# S7_Audio_IMU_uSD.net
KiCad netlist of a schematic drawn in Altium Designer
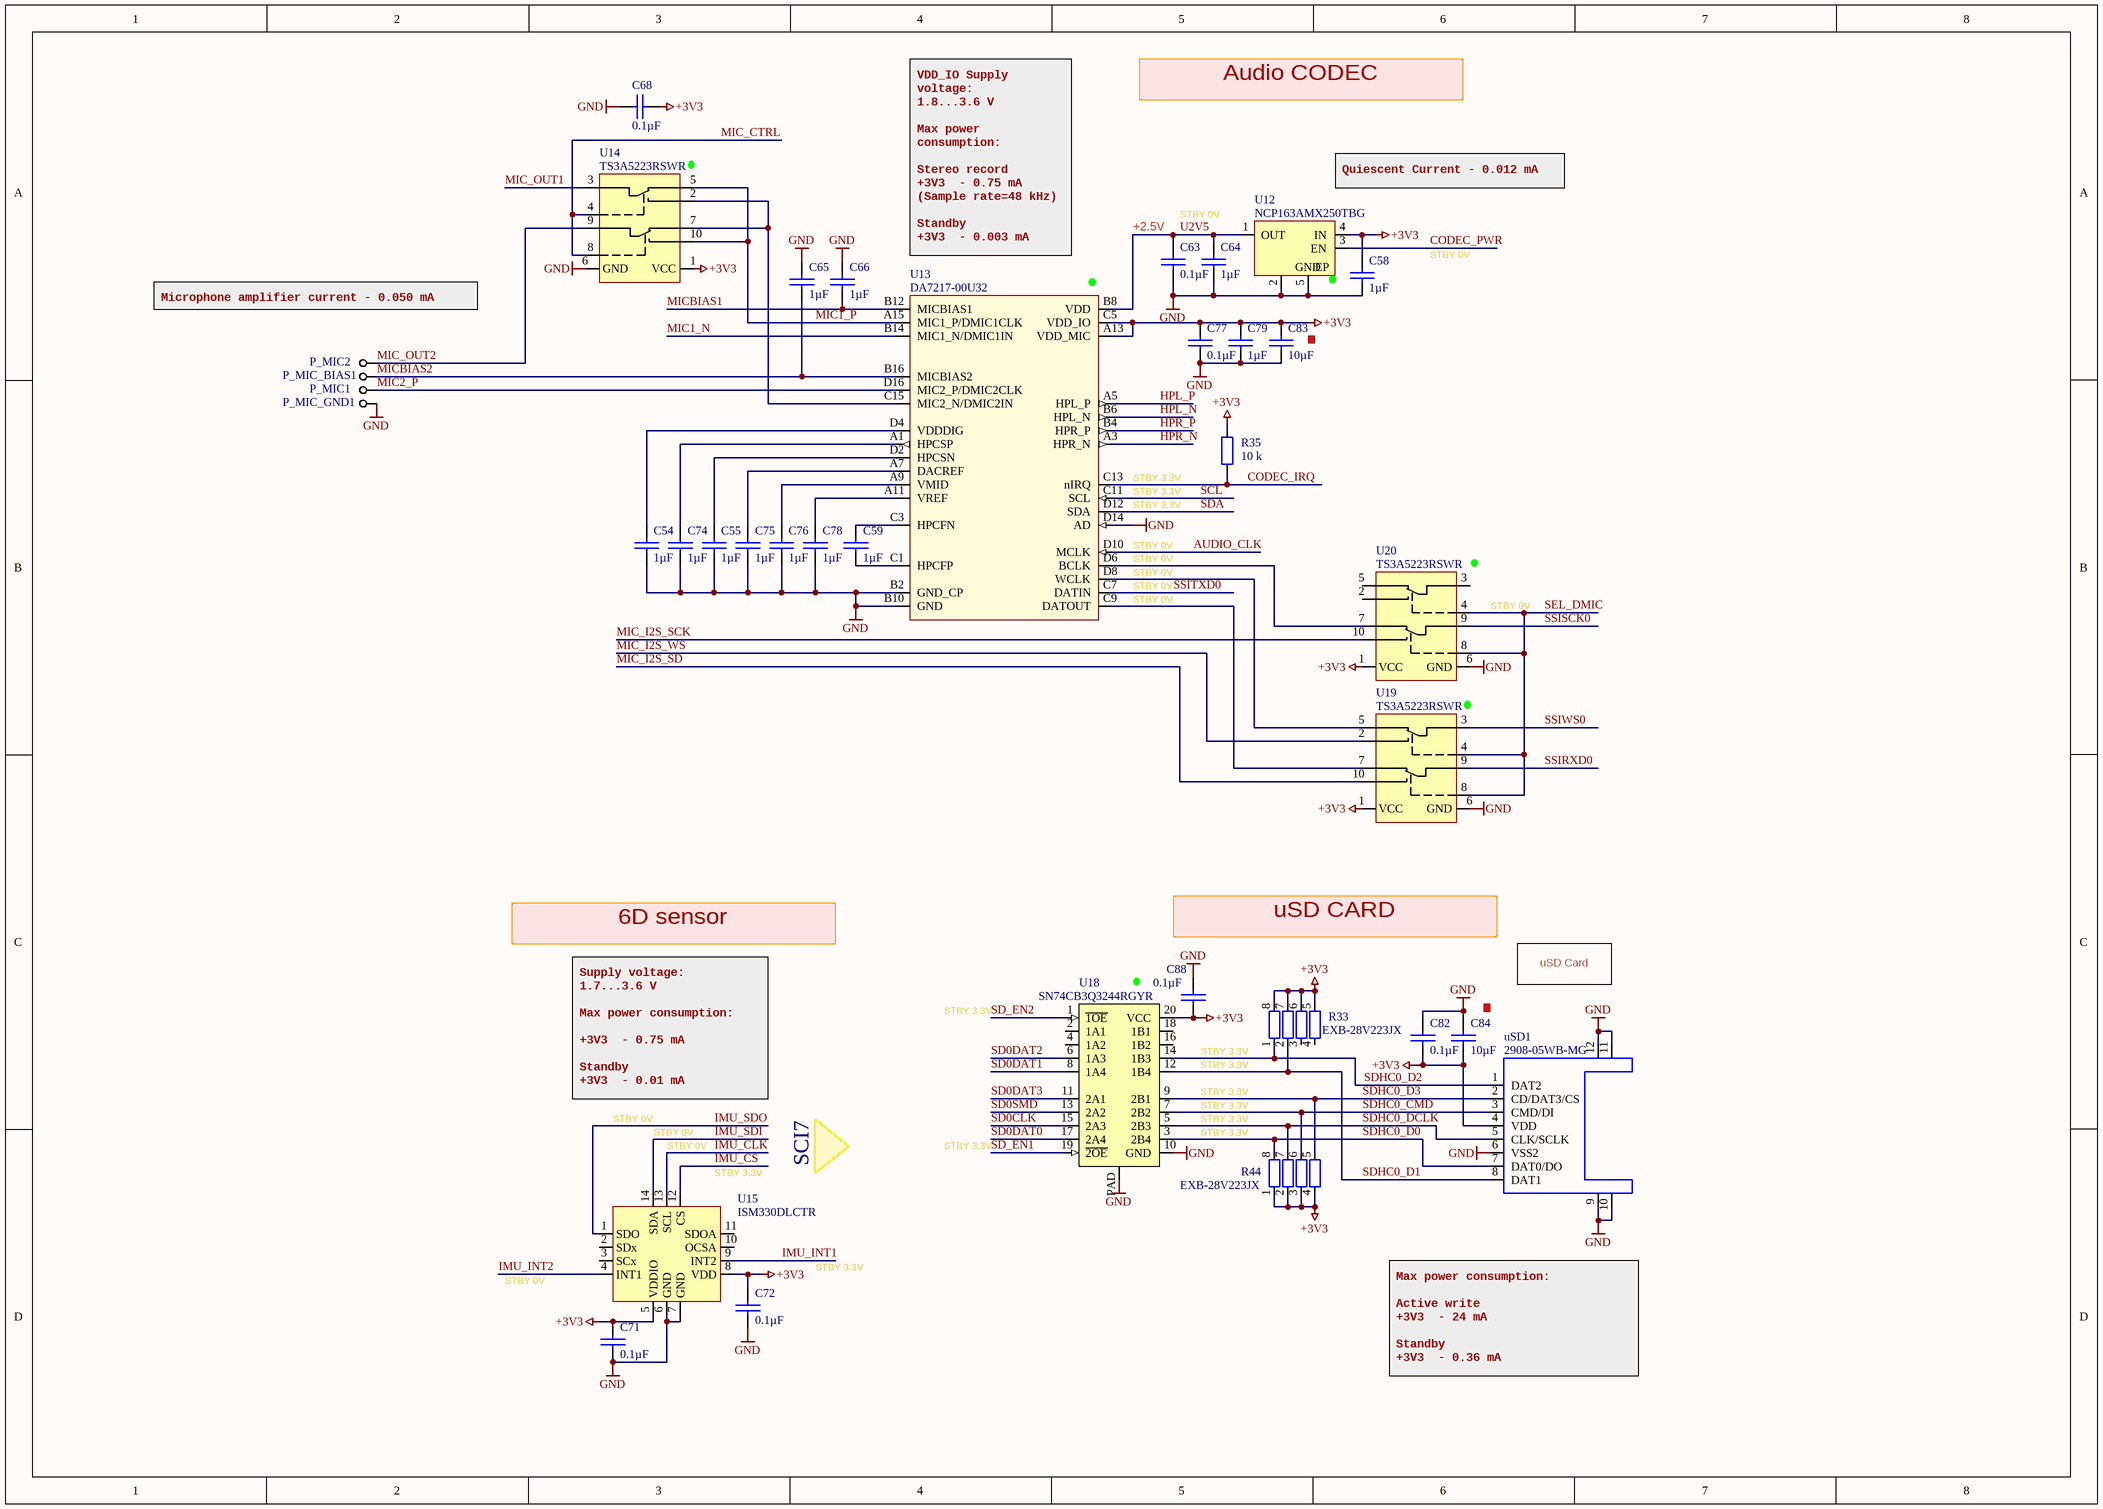
[diagram p0: S7_Audio_IMU_uSD.SchDoc]

(export (version "E")
  (design (tool "Eeschema 10.0.6"))
  (components
    (comp (ref "C54")
      (value "1µF")
      (footprint "0402 CAP")
      (description "1µF, ±20%, 25V, X5R, 0402 (1005 Metric), -55°C ~ 85°C, -, General Purpose")
      (fields (field (name "PART NUMBER") "TMK105BJ105MV-F") (field (name "MANUFACTURER") "Taiyo Yuden"))
      (libsource (lib "ea_PassivComps") (part "Capacitor"))
    )
    (comp (ref "C55")
      (value "1µF")
      (footprint "0402 CAP")
      (description "1µF, ±20%, 25V, X5R, 0402 (1005 Metric), -55°C ~ 85°C, -, General Purpose")
      (fields (field (name "PART NUMBER") "TMK105BJ105MV-F") (field (name "MANUFACTURER") "Taiyo Yuden"))
      (libsource (lib "ea_PassivComps") (part "Capacitor"))
    )
    (comp (ref "C58")
      (value "1µF")
      (footprint "0402 CAP")
      (description "1µF, ±20%, 25V, X5R, 0402 (1005 Metric), -55°C ~ 85°C, -, General Purpose")
      (fields (field (name "PART NUMBER") "TMK105BJ105MV-F") (field (name "MANUFACTURER") "Taiyo Yuden"))
      (libsource (lib "ea_PassivComps") (part "Capacitor"))
    )
    (comp (ref "C59")
      (value "1µF")
      (footprint "0402 CAP")
      (description "1µF, ±20%, 25V, X5R, 0402 (1005 Metric), -55°C ~ 85°C, -, General Purpose")
      (fields (field (name "PART NUMBER") "TMK105BJ105MV-F") (field (name "MANUFACTURER") "Taiyo Yuden"))
      (libsource (lib "ea_PassivComps") (part "Capacitor"))
    )
    (comp (ref "C63")
      (value "0.1µF")
      (footprint "0402 CAP")
      (description "0.1µF, ±10%, 50V, X7R, 0402 (1005 Metric), -55°C ~ 125°C, -, General Purpose")
      (fields
        (field (name "PART NUMBER") "0402B104K500CT")
        (field (name "MANUFACTURER") "Walsin Technology Corporation")
      )
      (libsource (lib "ea_PassivComps") (part "Capacitor"))
    )
    (comp (ref "C64")
      (value "1µF")
      (footprint "0402 CAP")
      (description "1µF, ±20%, 25V, X5R, 0402 (1005 Metric), -55°C ~ 85°C, -, General Purpose")
      (fields (field (name "PART NUMBER") "TMK105BJ105MV-F") (field (name "MANUFACTURER") "Taiyo Yuden"))
      (libsource (lib "ea_PassivComps") (part "Capacitor"))
    )
    (comp (ref "C65")
      (value "1µF")
      (footprint "0402 CAP")
      (description "1µF, ±20%, 25V, X5R, 0402 (1005 Metric), -55°C ~ 85°C, -, General Purpose")
      (fields (field (name "PART NUMBER") "TMK105BJ105MV-F") (field (name "MANUFACTURER") "Taiyo Yuden"))
      (libsource (lib "ea_PassivComps") (part "Capacitor"))
    )
    (comp (ref "C66")
      (value "1µF")
      (footprint "0402 CAP")
      (description "1µF, ±20%, 25V, X5R, 0402 (1005 Metric), -55°C ~ 85°C, -, General Purpose")
      (fields (field (name "PART NUMBER") "TMK105BJ105MV-F") (field (name "MANUFACTURER") "Taiyo Yuden"))
      (libsource (lib "ea_PassivComps") (part "Capacitor"))
    )
    (comp (ref "C68")
      (value "0.1µF")
      (footprint "0402 CAP")
      (description "0.1µF, ±10%, 50V, X7R, 0402 (1005 Metric), -55°C ~ 125°C, -, General Purpose")
      (fields
        (field (name "PART NUMBER") "0402B104K500CT")
        (field (name "MANUFACTURER") "Walsin Technology Corporation")
      )
      (libsource (lib "ea_PassivComps") (part "Capacitor"))
    )
    (comp (ref "C71")
      (value "0.1µF")
      (footprint "0402 CAP")
      (description "0.1µF, ±10%, 50V, X7R, 0402 (1005 Metric), -55°C ~ 125°C, -, General Purpose")
      (fields
        (field (name "PART NUMBER") "0402B104K500CT")
        (field (name "MANUFACTURER") "Walsin Technology Corporation")
      )
      (libsource (lib "ea_PassivComps") (part "Capacitor"))
    )
    (comp (ref "C72")
      (value "0.1µF")
      (footprint "0402 CAP")
      (description "0.1µF, ±10%, 50V, X7R, 0402 (1005 Metric), -55°C ~ 125°C, -, General Purpose")
      (fields
        (field (name "PART NUMBER") "0402B104K500CT")
        (field (name "MANUFACTURER") "Walsin Technology Corporation")
      )
      (libsource (lib "ea_PassivComps") (part "Capacitor"))
    )
    (comp (ref "C74")
      (value "1µF")
      (footprint "0402 CAP")
      (description "1µF, ±20%, 25V, X5R, 0402 (1005 Metric), -55°C ~ 85°C, -, General Purpose")
      (fields (field (name "PART NUMBER") "TMK105BJ105MV-F") (field (name "MANUFACTURER") "Taiyo Yuden"))
      (libsource (lib "ea_PassivComps") (part "Capacitor"))
    )
    (comp (ref "C75")
      (value "1µF")
      (footprint "0402 CAP")
      (description "1µF, ±20%, 25V, X5R, 0402 (1005 Metric), -55°C ~ 85°C, -, General Purpose")
      (fields (field (name "PART NUMBER") "TMK105BJ105MV-F") (field (name "MANUFACTURER") "Taiyo Yuden"))
      (libsource (lib "ea_PassivComps") (part "Capacitor"))
    )
    (comp (ref "C76")
      (value "1µF")
      (footprint "0402 CAP")
      (description "1µF, ±20%, 25V, X5R, 0402 (1005 Metric), -55°C ~ 85°C, -, General Purpose")
      (fields (field (name "PART NUMBER") "TMK105BJ105MV-F") (field (name "MANUFACTURER") "Taiyo Yuden"))
      (libsource (lib "ea_PassivComps") (part "Capacitor"))
    )
    (comp (ref "C77")
      (value "0.1µF")
      (footprint "0402 CAP")
      (description "0.1µF, ±10%, 50V, X7R, 0402 (1005 Metric), -55°C ~ 125°C, -, General Purpose")
      (fields
        (field (name "PART NUMBER") "0402B104K500CT")
        (field (name "MANUFACTURER") "Walsin Technology Corporation")
      )
      (libsource (lib "ea_PassivComps") (part "Capacitor"))
    )
    (comp (ref "C78")
      (value "1µF")
      (footprint "0402 CAP")
      (description "1µF, ±20%, 25V, X5R, 0402 (1005 Metric), -55°C ~ 85°C, -, General Purpose")
      (fields (field (name "PART NUMBER") "TMK105BJ105MV-F") (field (name "MANUFACTURER") "Taiyo Yuden"))
      (libsource (lib "ea_PassivComps") (part "Capacitor"))
    )
    (comp (ref "C79")
      (value "1µF")
      (footprint "0402 CAP")
      (description "1µF, ±20%, 25V, X5R, 0402 (1005 Metric), -55°C ~ 85°C, -, General Purpose")
      (fields (field (name "PART NUMBER") "TMK105BJ105MV-F") (field (name "MANUFACTURER") "Taiyo Yuden"))
      (libsource (lib "ea_PassivComps") (part "Capacitor"))
    )
    (comp (ref "C82")
      (value "0.1µF")
      (footprint "0402 CAP")
      (description "0.1µF, ±10%, 50V, X7R, 0402 (1005 Metric), -55°C ~ 125°C, -, General Purpose")
      (fields
        (field (name "PART NUMBER") "0402B104K500CT")
        (field (name "MANUFACTURER") "Walsin Technology Corporation")
      )
      (libsource (lib "ea_PassivComps") (part "Capacitor"))
    )
    (comp (ref "C83")
      (value "10µF")
      (footprint "0603 CAP")
      (description "10µF, ±10%, 16V, X5R, 0603 (1608 Metric), -55°C ~ 85°C, -, Automotive")
      (fields
        (field (name "PART NUMBER") "GRT188R61C106KE13D")
        (field (name "MANUFACTURER") "Murata Electronics North America")
      )
      (libsource (lib "ea_PassivComps") (part "Capacitor"))
    )
    (comp (ref "C84")
      (value "10µF")
      (footprint "0603 CAP")
      (description "10µF, ±10%, 16V, X5R, 0603 (1608 Metric), -55°C ~ 85°C, -, Automotive")
      (fields
        (field (name "PART NUMBER") "GRT188R61C106KE13D")
        (field (name "MANUFACTURER") "Murata Electronics North America")
      )
      (libsource (lib "ea_PassivComps") (part "Capacitor"))
    )
    (comp (ref "C88")
      (value "0.1µF")
      (footprint "0402 CAP")
      (description "0.1µF, ±10%, 50V, X7R, 0402 (1005 Metric), -55°C ~ 125°C, -, General Purpose")
      (fields
        (field (name "PART NUMBER") "0402B104K500CT")
        (field (name "MANUFACTURER") "Walsin Technology Corporation")
      )
      (libsource (lib "ea_PassivComps") (part "Capacitor"))
    )
    (comp (ref "P_MIC1")
      (value "PIN_TOP_1.5x2")
      (footprint "PIN_TOP_1.5x2")
      (description "Pin on TOP layer 1.5 x 2 mm")
      (libsource (lib "ea_Contacts") (part "PIN_TOP_1.5x2"))
    )
    (comp (ref "P_MIC2")
      (value "PIN_TOP_1.5x2")
      (footprint "PIN_TOP_1.5x2")
      (description "Pin on TOP layer 1.5 x 2 mm")
      (libsource (lib "ea_Contacts") (part "PIN_TOP_1.5x2"))
    )
    (comp (ref "P_MIC_BIAS1")
      (value "PIN_TOP_1.5x2")
      (footprint "PIN_TOP_1.5x2")
      (description "Pin on TOP layer 1.5 x 2 mm")
      (libsource (lib "ea_Contacts") (part "PIN_TOP_1.5x2"))
    )
    (comp (ref "P_MIC_GND1")
      (value "PIN_TOP_1.5x2")
      (footprint "PIN_TOP_1.5x2")
      (description "Pin on TOP layer 1.5 x 2 mm")
      (libsource (lib "ea_Contacts") (part "PIN_TOP_1.5x2"))
    )
    (comp (ref "R33")
      (value "EXB-28V223JX")
      (footprint "EXB28V 2x1 mm")
      (description "22k Ohm ±5%,  4 Resistor, -55°C ~ 125°C,(2.00mm x 1.00mm)")
      (fields (field (name "MANUFACTURER") "Panasonic Electronic Components") (field (name "TOLERANCE") "5%"))
      (libsource (lib "ea_Resistors") (part "EXB-28V223JX"))
    )
    (comp (ref "R35")
      (value "10 k")
      (footprint "0402")
      (fields
        (field (name "MANUFACTURER") "Stackpole Electronics Inc")
        (field (name "TOLERANCE") "±1%")
        (field (name "VOLTAGE") "75V")
      )
      (libsource (lib "ea_PassivComps") (part "Resistor"))
    )
    (comp (ref "R44")
      (value "EXB-28V223JX")
      (footprint "EXB28V 2x1 mm")
      (description "22k Ohm ±5%,  4 Resistor, -55°C ~ 125°C,(2.00mm x 1.00mm)")
      (fields (field (name "MANUFACTURER") "Panasonic Electronic Components") (field (name "TOLERANCE") "5%"))
      (libsource (lib "ea_Resistors") (part "EXB-28V223JX"))
    )
    (comp (ref "U12")
      (value "NCP163AMX250TBG")
      (footprint "4-XDFN")
      (description "LDO 2.5V, 250 mA, Vin < 5.5V, Iq < 20uA, -40..+125 C,  4-XDFN (1x1)")
      (fields
        (field (name "MANUFACTURER") "ON Semiconductor")
        (field (name "PARTNUM") "NCP163AMX250TBGOSCT-ND")
      )
      (libsource (lib "ea_IC_Power_Reg_Ref_Sw") (part "NCP163AMX250TBG"))
    )
    (comp (ref "U13")
      (value "DA7217-00U32")
      (footprint "Dilaog 34-WLCSP (4.57x1.98)")
      (description "Low power CODEC, 24 b, 2/2, I²C, I²S,  1.5V ~ 3.6V,  -25°C ~ 85°C, 34-WLCSP (4.57x1.98)")
      (fields
        (field (name "MANUFACTURER") "Dialog Semiconductor GmbH")
        (field (name "PARTNUM") "1564-1043-1-ND")
      )
      (libsource (lib "ea_IC_audio") (part "DA7217-00U32"))
    )
    (comp (ref "U14")
      (value "TS3A5223RSWR")
      (footprint "uQFN-10")
      (description "2 Circuit IC Switch 2:1 600 mOhm,-40°C ~ 85°C, 10-UQFN (1.8x1.4)")
      (fields (field (name "MANUFACTURER") "Texas Instruments") (field (name "PARTNUM") "296-35687-1-ND"))
      (libsource (lib "ea_IC_AnalogMux") (part "TS3A5223RSWR"))
    )
    (comp (ref "U15")
      (value "ISM330DLCTR")
      (footprint "LGA-14 BOSCH")
      (description "Accelerometer, Gyroscope, Temperature, 3 Axis Sensor I²C, SPI , -40°C ~ 85°C, 14-LGA (2.5x3)")
      (fields (field (name "MANUFACTURER") "STMicroelectronics") (field (name "PARTNUM") "497-17583-1-ND"))
      (libsource (lib "ea_IC_sensors") (part "ISM330DLCTR"))
    )
    (comp (ref "U18")
      (value "SN74CB3Q3244RGYR")
      (footprint "TI_PVQFN-N20")
      (description "Bus Switch 4 x 1:1, 2.3V ~ 3.6V,  -40°C ~ 85°C, 20-VQFN (3.5x4.5)")
      (fields (field (name "MANUFACTURER") "Texas Instruments") (field (name "PARTNUM") "296-19127-1-ND"))
      (libsource (lib "ea_IC_registers_buffers") (part "SN74CB3Q3244RGYR"))
    )
    (comp (ref "U19")
      (value "TS3A5223RSWR")
      (footprint "uQFN-10")
      (description "2 Circuit IC Switch 2:1 600 mOhm,-40°C ~ 85°C, 10-UQFN (1.8x1.4)")
      (fields (field (name "MANUFACTURER") "Texas Instruments") (field (name "PARTNUM") "296-35687-1-ND"))
      (libsource (lib "") (part "TS3A5223RSWR_1"))
    )
    (comp (ref "U20")
      (value "TS3A5223RSWR")
      (footprint "uQFN-10")
      (description "2 Circuit IC Switch 2:1 600 mOhm,-40°C ~ 85°C, 10-UQFN (1.8x1.4)")
      (fields (field (name "MANUFACTURER") "Texas Instruments") (field (name "PARTNUM") "296-35687-1-ND"))
      (libsource (lib "") (part "TS3A5223RSWR_1"))
    )
    (comp (ref "uSD1")
      (value "2908-05WB-MG")
      (footprint "2908-05WB-MG")
      (description "microSD cadr holder")
      (fields
        (field (name "MANUFACTURER") "Amphenol Commercial Products")
        (field (name "PARTNUM") "101-00660-68-6-1-ND")
      )
      (libsource (lib "ea_CARD_holders") (part "2908-05WB-MG"))
    )
  )
  (nets
    (net (code "1") (name "+3V3") (class "Default")
      (node (ref "C58") (pin "1") (pinfunction "1_1") (pintype "passive"))
      (node (ref "C68") (pin "2") (pinfunction "2_2") (pintype "passive"))
      (node (ref "C71") (pin "1") (pinfunction "1_1") (pintype "passive"))
      (node (ref "C72") (pin "1") (pinfunction "1_1") (pintype "passive"))
      (node (ref "C77") (pin "1") (pinfunction "1_1") (pintype "passive"))
      (node (ref "C79") (pin "1") (pinfunction "1_1") (pintype "passive"))
      (node (ref "C82") (pin "2") (pinfunction "2_2") (pintype "passive"))
      (node (ref "C83") (pin "1") (pinfunction "1_1") (pintype "passive"))
      (node (ref "C84") (pin "2") (pinfunction "2_2") (pintype "passive"))
      (node (ref "C88") (pin "2") (pinfunction "2_2") (pintype "passive"))
      (node (ref "R33") (pin "5") (pinfunction "5_5") (pintype "passive"))
      (node (ref "R33") (pin "6") (pinfunction "6_6") (pintype "passive"))
      (node (ref "R33") (pin "7") (pinfunction "7_7") (pintype "passive"))
      (node (ref "R33") (pin "8") (pinfunction "8_8") (pintype "passive"))
      (node (ref "R35") (pin "2") (pinfunction "2_2") (pintype "passive"))
      (node (ref "R44") (pin "1") (pinfunction "1_1") (pintype "passive"))
      (node (ref "R44") (pin "2") (pinfunction "2_2") (pintype "passive"))
      (node (ref "R44") (pin "3") (pinfunction "3_3") (pintype "passive"))
      (node (ref "R44") (pin "4") (pinfunction "4_4") (pintype "passive"))
      (node (ref "U12") (pin "4") (pinfunction "IN_4") (pintype "power_in"))
      (node (ref "U13") (pin "A13") (pinfunction "VDD_MIC_A13") (pintype "power_in"))
      (node (ref "U13") (pin "C5") (pinfunction "VDD_IO_C5") (pintype "power_in"))
      (node (ref "U14") (pin "1") (pinfunction "VCC_1") (pintype "passive"))
      (node (ref "U15") (pin "5") (pinfunction "VDDIO_5") (pintype "passive"))
      (node (ref "U15") (pin "8") (pinfunction "VDD_8") (pintype "passive"))
      (node (ref "U18") (pin "20") (pinfunction "VCC_20") (pintype "power_in"))
      (node (ref "U19") (pin "1") (pinfunction "VCC_1") (pintype "passive"))
      (node (ref "U20") (pin "1") (pinfunction "VCC_1") (pintype "passive"))
      (node (ref "uSD1") (pin "4") (pinfunction "VDD_4") (pintype "passive"))
    )
    (net (code "2") (name "/AUDIO_CLK") (class "Default")
      (node (ref "U13") (pin "D10") (pinfunction "MCLK_D10") (pintype "input"))
    )
    (net (code "3") (name "/CODEC_IRQ") (class "Default")
      (node (ref "R35") (pin "1") (pinfunction "1_1") (pintype "passive"))
      (node (ref "U13") (pin "C13") (pinfunction "nIRQ_C13") (pintype "bidirectional"))
    )
    (net (code "4") (name "/CODEC_PWR") (class "Default")
      (node (ref "U12") (pin "3") (pinfunction "EN_3") (pintype "power_in"))
    )
    (net (code "5") (name "/HPL_N") (class "Default")
      (node (ref "U13") (pin "B6") (pinfunction "HPL_N_B6") (pintype "output"))
    )
    (net (code "6") (name "/HPL_P") (class "Default")
      (node (ref "U13") (pin "A5") (pinfunction "HPL_P_A5") (pintype "output"))
    )
    (net (code "7") (name "/HPR_N") (class "Default")
      (node (ref "U13") (pin "A3") (pinfunction "HPR_N_A3") (pintype "output"))
    )
    (net (code "8") (name "/HPR_P") (class "Default")
      (node (ref "U13") (pin "B4") (pinfunction "HPR_P_B4") (pintype "output"))
    )
    (net (code "9") (name "/IMU_CLK") (class "Default")
      (node (ref "U15") (pin "13") (pinfunction "SCL_13") (pintype "passive"))
    )
    (net (code "10") (name "/IMU_CS") (class "Default")
      (node (ref "U15") (pin "12") (pinfunction "CS_12") (pintype "passive"))
    )
    (net (code "11") (name "/IMU_INT1") (class "Default")
      (node (ref "U15") (pin "9") (pinfunction "INT2_9") (pintype "passive"))
    )
    (net (code "12") (name "/IMU_INT2") (class "Default")
      (node (ref "U15") (pin "4") (pinfunction "INT1_4") (pintype "passive"))
    )
    (net (code "13") (name "/IMU_SDI") (class "Default")
      (node (ref "U15") (pin "14") (pinfunction "SDA_14") (pintype "passive"))
    )
    (net (code "14") (name "/IMU_SDO") (class "Default")
      (node (ref "U15") (pin "1") (pinfunction "SDO_1") (pintype "passive"))
    )
    (net (code "15") (name "/MIC1_N") (class "Default")
      (node (ref "U13") (pin "B14") (pinfunction "MIC1_N/DMIC1IN_B14") (pintype "bidirectional"))
    )
    (net (code "16") (name "/MIC1_P") (class "Default")
      (node (ref "U13") (pin "A15") (pinfunction "MIC1_P/DMIC1CLK_A15") (pintype "bidirectional"))
      (node (ref "U14") (pin "10") (pinfunction "NO2_10") (pintype "passive"))
      (node (ref "U14") (pin "5") (pinfunction "NC1_5") (pintype "passive"))
    )
    (net (code "17") (name "/MIC2_P") (class "Default")
      (node (ref "P_MIC1") (pin "1") (pinfunction "1_1") (pintype "passive"))
      (node (ref "U13") (pin "D16") (pinfunction "MIC2_P/DMIC2CLK_D16") (pintype "bidirectional"))
    )
    (net (code "18") (name "/MICBIAS1") (class "Default")
      (node (ref "C66") (pin "2") (pinfunction "2_2") (pintype "passive"))
      (node (ref "U13") (pin "B12") (pinfunction "MICBIAS1_B12") (pintype "bidirectional"))
    )
    (net (code "19") (name "/MICBIAS2") (class "Default")
      (node (ref "C65") (pin "2") (pinfunction "2_2") (pintype "passive"))
      (node (ref "P_MIC_BIAS1") (pin "1") (pinfunction "1_1") (pintype "passive"))
      (node (ref "U13") (pin "B16") (pinfunction "MICBIAS2_B16") (pintype "bidirectional"))
    )
    (net (code "20") (name "/MIC_CTRL") (class "Default")
      (node (ref "U14") (pin "4") (pinfunction "SEL1_4") (pintype "passive"))
      (node (ref "U14") (pin "8") (pinfunction "SEL2_8") (pintype "passive"))
    )
    (net (code "21") (name "/MIC_I2S_SCK") (class "Default")
      (node (ref "U20") (pin "10") (pinfunction "NO2_10") (pintype "passive"))
    )
    (net (code "22") (name "/MIC_I2S_SD") (class "Default")
      (node (ref "U19") (pin "10") (pinfunction "NO2_10") (pintype "passive"))
    )
    (net (code "23") (name "/MIC_I2S_WS") (class "Default")
      (node (ref "U19") (pin "2") (pinfunction "NO1_2") (pintype "passive"))
    )
    (net (code "24") (name "/MIC_OUT1") (class "Default")
      (node (ref "U14") (pin "3") (pinfunction "COM1_3") (pintype "passive"))
    )
    (net (code "25") (name "/MIC_OUT2") (class "Default")
      (node (ref "P_MIC2") (pin "1") (pinfunction "1_1") (pintype "passive"))
      (node (ref "U14") (pin "9") (pinfunction "COM2_9") (pintype "passive"))
    )
    (net (code "26") (name "/SCL") (class "Default")
      (node (ref "U13") (pin "C11") (pinfunction "SCL_C11") (pintype "input"))
    )
    (net (code "27") (name "/SD0CLK") (class "Default")
      (node (ref "U18") (pin "15") (pinfunction "2A3_15") (pintype "bidirectional"))
    )
    (net (code "28") (name "/SD0DAT0") (class "Default")
      (node (ref "U18") (pin "17") (pinfunction "2A4_17") (pintype "bidirectional"))
    )
    (net (code "29") (name "/SD0DAT1") (class "Default")
      (node (ref "U18") (pin "8") (pinfunction "1A4_8") (pintype "bidirectional"))
    )
    (net (code "30") (name "/SD0DAT2") (class "Default")
      (node (ref "U18") (pin "6") (pinfunction "1A3_6") (pintype "bidirectional"))
    )
    (net (code "31") (name "/SD0DAT3") (class "Default")
      (node (ref "U18") (pin "11") (pinfunction "2A1_11") (pintype "bidirectional"))
    )
    (net (code "32") (name "/SD0SMD") (class "Default")
      (node (ref "U18") (pin "13") (pinfunction "2A2_13") (pintype "bidirectional"))
    )
    (net (code "33") (name "/SDA") (class "Default")
      (node (ref "U13") (pin "D12") (pinfunction "SDA_D12") (pintype "bidirectional"))
    )
    (net (code "34") (name "/SDHC0_CMD") (class "Default")
      (node (ref "R44") (pin "6") (pinfunction "6_6") (pintype "passive"))
      (node (ref "U18") (pin "7") (pinfunction "2B2_7") (pintype "bidirectional"))
      (node (ref "uSD1") (pin "3") (pinfunction "CMD/DI_3") (pintype "passive"))
    )
    (net (code "35") (name "/SDHC0_D0") (class "Default")
      (node (ref "R44") (pin "8") (pinfunction "8_8") (pintype "passive"))
      (node (ref "U18") (pin "3") (pinfunction "2B4_3") (pintype "bidirectional"))
      (node (ref "uSD1") (pin "7") (pinfunction "DAT0/DO_7") (pintype "passive"))
    )
    (net (code "36") (name "/SDHC0_D1") (class "Default")
      (node (ref "R33") (pin "2") (pinfunction "2_2") (pintype "passive"))
      (node (ref "U18") (pin "12") (pinfunction "1B4_12") (pintype "bidirectional"))
      (node (ref "uSD1") (pin "8") (pinfunction "DAT1_8") (pintype "passive"))
    )
    (net (code "37") (name "/SDHC0_D2") (class "Default")
      (node (ref "R33") (pin "1") (pinfunction "1_1") (pintype "passive"))
      (node (ref "U18") (pin "14") (pinfunction "1B3_14") (pintype "bidirectional"))
      (node (ref "uSD1") (pin "1") (pinfunction "DAT2_1") (pintype "passive"))
    )
    (net (code "38") (name "/SDHC0_D3") (class "Default")
      (node (ref "R44") (pin "5") (pinfunction "5_5") (pintype "passive"))
      (node (ref "U18") (pin "9") (pinfunction "2B1_9") (pintype "bidirectional"))
      (node (ref "uSD1") (pin "2") (pinfunction "CD/DAT3/CS_2") (pintype "passive"))
    )
    (net (code "39") (name "/SDHC0_DCLK") (class "Default")
      (node (ref "R44") (pin "7") (pinfunction "7_7") (pintype "passive"))
      (node (ref "U18") (pin "5") (pinfunction "2B3_5") (pintype "bidirectional"))
      (node (ref "uSD1") (pin "5") (pinfunction "CLK/SCLK_5") (pintype "passive"))
    )
    (net (code "40") (name "/SD_EN1") (class "Default")
      (node (ref "U18") (pin "19") (pinfunction "~{2OE}_19") (pintype "input"))
    )
    (net (code "41") (name "/SD_EN2") (class "Default")
      (node (ref "U18") (pin "1") (pinfunction "~{1OE}_1") (pintype "input"))
    )
    (net (code "42") (name "/SEL_DMIC") (class "Default")
      (node (ref "U19") (pin "4") (pinfunction "SEL1_4") (pintype "passive"))
      (node (ref "U19") (pin "8") (pinfunction "SEL2_8") (pintype "passive"))
      (node (ref "U20") (pin "4") (pinfunction "SEL1_4") (pintype "passive"))
      (node (ref "U20") (pin "8") (pinfunction "SEL2_8") (pintype "passive"))
    )
    (net (code "43") (name "/SSIRXD0") (class "Default")
      (node (ref "U19") (pin "9") (pinfunction "COM2_9") (pintype "passive"))
    )
    (net (code "44") (name "/SSISCK0") (class "Default")
      (node (ref "U20") (pin "9") (pinfunction "COM2_9") (pintype "passive"))
    )
    (net (code "45") (name "/SSITXD0") (class "Default")
      (node (ref "U13") (pin "C7") (pinfunction "DATIN_C7") (pintype "bidirectional"))
    )
    (net (code "46") (name "/SSIWS0") (class "Default")
      (node (ref "U19") (pin "3") (pinfunction "COM1_3") (pintype "passive"))
    )
    (net (code "47") (name "/U2V5") (class "Default")
      (node (ref "C63") (pin "1") (pinfunction "1_1") (pintype "passive"))
      (node (ref "C64") (pin "1") (pinfunction "1_1") (pintype "passive"))
      (node (ref "U12") (pin "1") (pinfunction "OUT_1") (pintype "power_in"))
      (node (ref "U13") (pin "B8") (pinfunction "VDD_B8") (pintype "power_in"))
    )
    (net (code "48") (name "GND") (class "Default")
      (node (ref "C54") (pin "2") (pinfunction "2_2") (pintype "passive"))
      (node (ref "C55") (pin "2") (pinfunction "2_2") (pintype "passive"))
      (node (ref "C58") (pin "2") (pinfunction "2_2") (pintype "passive"))
      (node (ref "C63") (pin "2") (pinfunction "2_2") (pintype "passive"))
      (node (ref "C64") (pin "2") (pinfunction "2_2") (pintype "passive"))
      (node (ref "C65") (pin "1") (pinfunction "1_1") (pintype "passive"))
      (node (ref "C66") (pin "1") (pinfunction "1_1") (pintype "passive"))
      (node (ref "C68") (pin "1") (pinfunction "1_1") (pintype "passive"))
      (node (ref "C71") (pin "2") (pinfunction "2_2") (pintype "passive"))
      (node (ref "C72") (pin "2") (pinfunction "2_2") (pintype "passive"))
      (node (ref "C74") (pin "2") (pinfunction "2_2") (pintype "passive"))
      (node (ref "C75") (pin "2") (pinfunction "2_2") (pintype "passive"))
      (node (ref "C76") (pin "2") (pinfunction "2_2") (pintype "passive"))
      (node (ref "C77") (pin "2") (pinfunction "2_2") (pintype "passive"))
      (node (ref "C78") (pin "2") (pinfunction "2_2") (pintype "passive"))
      (node (ref "C79") (pin "2") (pinfunction "2_2") (pintype "passive"))
      (node (ref "C82") (pin "1") (pinfunction "1_1") (pintype "passive"))
      (node (ref "C83") (pin "2") (pinfunction "2_2") (pintype "passive"))
      (node (ref "C84") (pin "1") (pinfunction "1_1") (pintype "passive"))
      (node (ref "C88") (pin "1") (pinfunction "1_1") (pintype "passive"))
      (node (ref "P_MIC_GND1") (pin "1") (pinfunction "1_1") (pintype "passive"))
      (node (ref "U12") (pin "2") (pinfunction "GND_2") (pintype "power_in"))
      (node (ref "U12") (pin "5") (pinfunction "EP_5") (pintype "power_in"))
      (node (ref "U13") (pin "B10") (pinfunction "GND_B10") (pintype "power_in"))
      (node (ref "U13") (pin "B2") (pinfunction "GND_CP_B2") (pintype "power_in"))
      (node (ref "U13") (pin "D14") (pinfunction "AD_D14") (pintype "input"))
      (node (ref "U14") (pin "6") (pinfunction "GND_6") (pintype "passive"))
      (node (ref "U15") (pin "6") (pinfunction "GND_6") (pintype "passive"))
      (node (ref "U15") (pin "7") (pinfunction "GND_7") (pintype "passive"))
      (node (ref "U18") (pin "10") (pinfunction "GND_10") (pintype "power_in"))
      (node (ref "U18") (pin "PAD") (pinfunction "PAD_PAD") (pintype "passive"))
      (node (ref "U19") (pin "6") (pinfunction "GND_6") (pintype "passive"))
      (node (ref "U20") (pin "6") (pinfunction "GND_6") (pintype "passive"))
      (node (ref "uSD1") (pin "10") (pinfunction "WP_10") (pintype "passive"))
      (node (ref "uSD1") (pin "11") (pinfunction "GND_11") (pintype "passive"))
      (node (ref "uSD1") (pin "12") (pinfunction "GND_12") (pintype "passive"))
      (node (ref "uSD1") (pin "6") (pinfunction "VSS2_6") (pintype "passive"))
      (node (ref "uSD1") (pin "9") (pintype "passive"))
    )
    (net (code "49") (name "Net-(U13-BCLK)") (class "Default")
      (node (ref "U13") (pin "D6") (pinfunction "BCLK_D6") (pintype "bidirectional"))
      (node (ref "U20") (pin "7") (pinfunction "NC2_7") (pintype "passive"))
    )
    (net (code "50") (name "Net-(U13-DACREF)") (class "Default")
      (node (ref "C75") (pin "1") (pinfunction "1_1") (pintype "passive"))
      (node (ref "U13") (pin "A7") (pinfunction "DACREF_A7") (pintype "power_in"))
    )
    (net (code "51") (name "Net-(U13-DATOUT)") (class "Default")
      (node (ref "U13") (pin "C9") (pinfunction "DATOUT_C9") (pintype "bidirectional"))
      (node (ref "U19") (pin "7") (pinfunction "NC2_7") (pintype "passive"))
    )
    (net (code "52") (name "Net-(U13-HPCFN)") (class "Default")
      (node (ref "C59") (pin "1") (pinfunction "1_1") (pintype "passive"))
      (node (ref "U13") (pin "C3") (pinfunction "HPCFN_C3") (pintype "bidirectional"))
    )
    (net (code "53") (name "Net-(U13-HPCFP)") (class "Default")
      (node (ref "C59") (pin "2") (pinfunction "2_2") (pintype "passive"))
      (node (ref "U13") (pin "C1") (pinfunction "HPCFP_C1") (pintype "bidirectional"))
    )
    (net (code "54") (name "Net-(U13-HPCSN)") (class "Default")
      (node (ref "C55") (pin "1") (pinfunction "1_1") (pintype "passive"))
      (node (ref "U13") (pin "D2") (pinfunction "HPCSN_D2") (pintype "bidirectional"))
    )
    (net (code "55") (name "Net-(U13-HPCSP)") (class "Default")
      (node (ref "C74") (pin "1") (pinfunction "1_1") (pintype "passive"))
      (node (ref "U13") (pin "A1") (pinfunction "HPCSP_A1") (pintype "output"))
    )
    (net (code "56") (name "Net-(U13-MIC2_N{slash}DMIC2IN)") (class "Default")
      (node (ref "U13") (pin "C15") (pinfunction "MIC2_N/DMIC2IN_C15") (pintype "bidirectional"))
      (node (ref "U14") (pin "2") (pinfunction "NO1_2") (pintype "passive"))
      (node (ref "U14") (pin "7") (pinfunction "NC2_7") (pintype "passive"))
    )
    (net (code "57") (name "Net-(U13-VDDDIG)") (class "Default")
      (node (ref "C54") (pin "1") (pinfunction "1_1") (pintype "passive"))
      (node (ref "U13") (pin "D4") (pinfunction "VDDDIG_D4") (pintype "power_in"))
    )
    (net (code "58") (name "Net-(U13-VMID)") (class "Default")
      (node (ref "C76") (pin "1") (pinfunction "1_1") (pintype "passive"))
      (node (ref "U13") (pin "A9") (pinfunction "VMID_A9") (pintype "power_in"))
    )
    (net (code "59") (name "Net-(U13-VREF)") (class "Default")
      (node (ref "C78") (pin "1") (pinfunction "1_1") (pintype "passive"))
      (node (ref "U13") (pin "A11") (pinfunction "VREF_A11") (pintype "power_in"))
    )
    (net (code "60") (name "Net-(U13-WCLK)") (class "Default")
      (node (ref "U13") (pin "D8") (pinfunction "WCLK_D8") (pintype "bidirectional"))
      (node (ref "U19") (pin "5") (pinfunction "NC1_5") (pintype "passive"))
    )
    (net (code "61") (name "unconnected-(R33-Pad3)") (class "Default")
      (node (ref "R33") (pin "3") (pinfunction "3_3") (pintype "passive"))
    )
    (net (code "62") (name "unconnected-(R33-Pad4)") (class "Default")
      (node (ref "R33") (pin "4") (pinfunction "4_4") (pintype "passive"))
    )
    (net (code "63") (name "unconnected-(U15-OCSA-Pad10)") (class "Default")
      (node (ref "U15") (pin "10") (pinfunction "OCSA_10") (pintype "passive"))
    )
    (net (code "64") (name "unconnected-(U15-SCx-Pad3)") (class "Default")
      (node (ref "U15") (pin "3") (pinfunction "SCx_3") (pintype "passive"))
    )
    (net (code "65") (name "unconnected-(U15-SDOA-Pad11)") (class "Default")
      (node (ref "U15") (pin "11") (pinfunction "SDOA_11") (pintype "passive"))
    )
    (net (code "66") (name "unconnected-(U15-SDx-Pad2)") (class "Default")
      (node (ref "U15") (pin "2") (pinfunction "SDx_2") (pintype "passive"))
    )
    (net (code "67") (name "unconnected-(U18-1A1-Pad2)") (class "Default")
      (node (ref "U18") (pin "2") (pinfunction "1A1_2") (pintype "bidirectional"))
    )
    (net (code "68") (name "unconnected-(U18-1A2-Pad4)") (class "Default")
      (node (ref "U18") (pin "4") (pinfunction "1A2_4") (pintype "bidirectional"))
    )
    (net (code "69") (name "unconnected-(U18-1B1-Pad18)") (class "Default")
      (node (ref "U18") (pin "18") (pinfunction "1B1_18") (pintype "bidirectional"))
    )
    (net (code "70") (name "unconnected-(U18-1B2-Pad16)") (class "Default")
      (node (ref "U18") (pin "16") (pinfunction "1B2_16") (pintype "bidirectional"))
    )
    (net (code "71") (name "unconnected-(U20-COM1-Pad3)") (class "Default")
      (node (ref "U20") (pin "3") (pinfunction "COM1_3") (pintype "passive"))
    )
    (net (code "72") (name "unconnected-(U20-NC1-Pad5)") (class "Default")
      (node (ref "U20") (pin "5") (pinfunction "NC1_5") (pintype "passive"))
    )
    (net (code "73") (name "unconnected-(U20-NO1-Pad2)") (class "Default")
      (node (ref "U20") (pin "2") (pinfunction "NO1_2") (pintype "passive"))
    )
  )
)
